# SMPS.net
KiCad netlist of a schematic drawn in Altium Designer
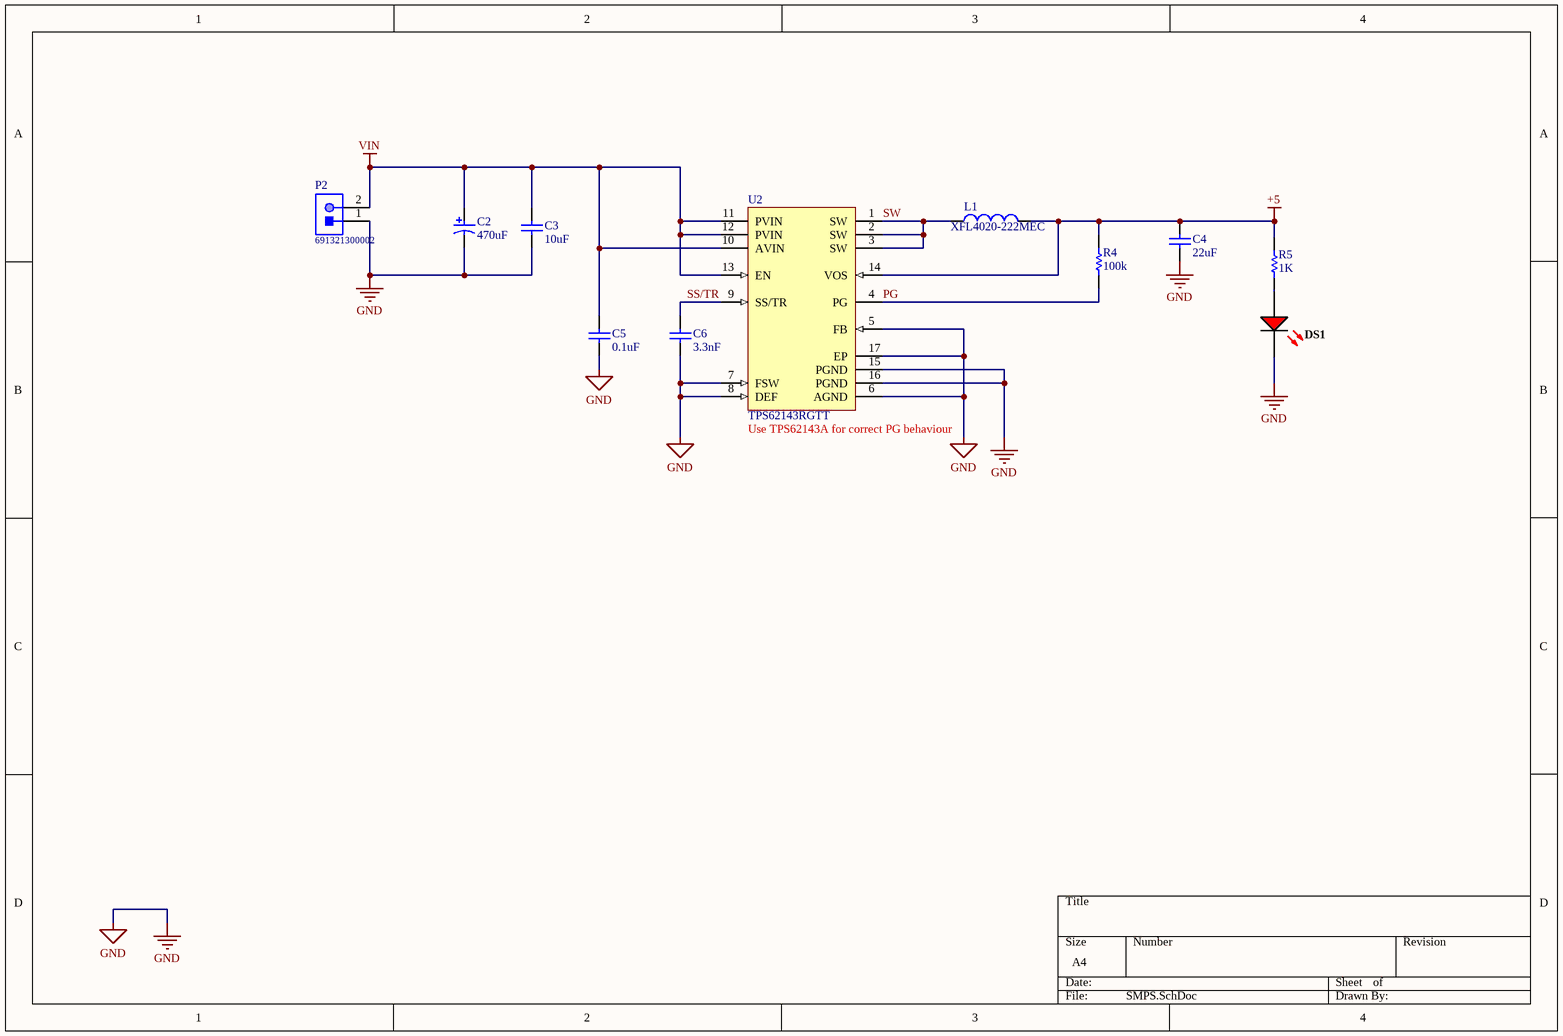
[diagram p0: SMPS.SchDoc]

(export (version "E")
  (design (tool "Eeschema 10.0.6"))
  (components
    (comp (ref "C2")
      (value "470uF")
      (footprint "PNSC-FK-V-F_V")
      (fields (field (name "MANUFACTURER") "Panasonic"))
      (libsource (lib "Altium Content Vault") (part "CAP-P-2"))
    )
    (comp (ref "C3")
      (value "10uF")
      (footprint "CAPC1210(3225)210_M")
      (description "CAP 10uF 35V ±20% 1210 (3225 Metric) Thickness 2.1mm SMD")
      (fields (field (name "TOLERANCE") "Â±20%"))
      (libsource (lib "Altium Content Vault") (part "CAP"))
    )
    (comp (ref "C4")
      (value "22uF")
      (footprint "CAPC2013X95X45ML15T25")
      (fields (field (name "MANUFACTURER") "Murata") (field (name "PART NUMBER") "GRM219R61A226MEA0D"))
      (libsource (lib "Altium Content Vault") (part "CAP"))
    )
    (comp (ref "C5")
      (value "0.1uF")
      (footprint "CAPC1608X87X35NL15T15")
      (fields (field (name "PART NUMBER") "C0603X104K5RACTU") (field (name "MANUFACTURER") "Kemet"))
      (libsource (lib "Altium Content Vault") (part "CAP"))
    )
    (comp (ref "C6")
      (value "3.3nF")
      (footprint "CAPC1608X87X35NL15T15")
      (fields (field (name "PART NUMBER") "C0603C332K5RAC7867") (field (name "MANUFACTURER") "Kemet"))
      (libsource (lib "Altium Content Vault") (part "CAP"))
    )
    (comp (ref "DS1")
      (value "APG1608SURKC/T")
      (footprint "KING-LED0603-25-RED_V")
      (fields (field (name "MANUFACTURER") "Kingbright"))
      (libsource (lib "Altium Content Vault") (part "KING-LED_RED_A1K2-2"))
    )
    (comp (ref "L1")
      (value "XFL4020-222MEC")
      (footprint "COIL-IND-2_V")
      (fields (field (name "MANUFACTURER") "Coilcraft") (field (name "TOLERANCE") "20%"))
      (libsource (lib "Altium Content Vault") (part "IND-2"))
    )
    (comp (ref "P2")
      (value "691321300002")
      (footprint "691321300002")
      (description "Serie 321 - 3.81mm Vertical PCB Header WR-TBL, 2 pin")
      (fields (field (name "MANUFACTURER") "Wurth Elektronik") (field (name "PUBLISHER") "WurthElektronik"))
      (libsource (lib "Altium Content Vault") (part "WE-CN-1P-M-R2"))
    )
    (comp (ref "R4")
      (value "100k")
      (footprint "RESC1608X55X25ML10T15")
      (description "Chip Resistor, 100 KOhm, +/- 1%, 0.1 W, -55 to 155 degC, 0603 (1608 Metric), RoHS, Tape and Reel")
      (fields (field (name "MANUFACTURER") "Yageo") (field (name "TOLERANCE") "1%"))
      (libsource (lib "Altium Content Vault") (part "RES-2"))
    )
    (comp (ref "R5")
      (value "1K")
      (footprint "RESC1608X55X30LL15T15")
      (fields (field (name "PART NUMBER") "ERJ-3EKF1001V") (field (name "MANUFACTURER") "Panasonic"))
      (libsource (lib "Altium Content Vault") (part "RES"))
    )
    (comp (ref "U2")
      (value "TPS62143RGTT")
      (footprint "RGT0016C_V")
      (fields (field (name "MANUFACTURER") "Texas Instruments"))
      (libsource (lib "Altium Content Vault") (part "TI-TPS62143RGT16-1700X1700TP"))
    )
  )
  (nets
    (net (code "1") (name "+5") (class "Default")
      (node (ref "C4") (pin "2") (pinfunction "2_2") (pintype "passive"))
      (node (ref "L1") (pin "2") (pinfunction "2_2") (pintype "passive"))
      (node (ref "R4") (pin "2") (pinfunction "2_2") (pintype "passive"))
      (node (ref "R5") (pin "2") (pinfunction "2_2") (pintype "passive"))
      (node (ref "U2") (pin "14") (pinfunction "VOS_14") (pintype "input"))
    )
    (net (code "2") (name "/PG") (class "Default")
      (node (ref "R4") (pin "1") (pinfunction "1_1") (pintype "passive"))
      (node (ref "U2") (pin "4") (pinfunction "PG_4") (pintype "tri_state"))
    )
    (net (code "3") (name "/SS{slash}TR") (class "Default")
      (node (ref "C6") (pin "2") (pinfunction "2_2") (pintype "passive"))
      (node (ref "U2") (pin "9") (pinfunction "SS/TR_9") (pintype "input"))
    )
    (net (code "4") (name "/SW") (class "Default")
      (node (ref "L1") (pin "1") (pinfunction "1_1") (pintype "passive"))
      (node (ref "U2") (pin "1") (pinfunction "SW_1") (pintype "power_in"))
      (node (ref "U2") (pin "2") (pinfunction "SW_2") (pintype "power_in"))
      (node (ref "U2") (pin "3") (pinfunction "SW_3") (pintype "power_in"))
    )
    (net (code "5") (name "GND") (class "Default")
      (node (ref "C2") (pin "2") (pinfunction "2_2") (pintype "passive"))
      (node (ref "C3") (pin "1") (pinfunction "1_1") (pintype "passive"))
      (node (ref "C4") (pin "1") (pinfunction "1_1") (pintype "passive"))
      (node (ref "C5") (pin "2") (pinfunction "2_2") (pintype "passive"))
      (node (ref "C6") (pin "1") (pinfunction "1_1") (pintype "passive"))
      (node (ref "DS1") (pin "2") (pinfunction "K_2") (pintype "passive"))
      (node (ref "P2") (pin "1") (pinfunction "1_1") (pintype "passive"))
      (node (ref "U2") (pin "15") (pinfunction "PGND_15") (pintype "power_in"))
      (node (ref "U2") (pin "16") (pinfunction "PGND_16") (pintype "power_in"))
      (node (ref "U2") (pin "17") (pinfunction "EP_17") (pintype "power_in"))
      (node (ref "U2") (pin "5") (pinfunction "FB_5") (pintype "input"))
      (node (ref "U2") (pin "6") (pinfunction "AGND_6") (pintype "power_in"))
      (node (ref "U2") (pin "7") (pinfunction "FSW_7") (pintype "input"))
      (node (ref "U2") (pin "8") (pinfunction "DEF_8") (pintype "input"))
    )
    (net (code "6") (name "Net-(DS1-A)") (class "Default")
      (node (ref "DS1") (pin "1") (pinfunction "A_1") (pintype "passive"))
      (node (ref "R5") (pin "1") (pinfunction "1_1") (pintype "passive"))
    )
    (net (code "7") (name "VIN") (class "Default")
      (node (ref "C2") (pin "1") (pinfunction "1_1") (pintype "passive"))
      (node (ref "C3") (pin "2") (pinfunction "2_2") (pintype "passive"))
      (node (ref "C5") (pin "1") (pinfunction "1_1") (pintype "passive"))
      (node (ref "P2") (pin "2") (pinfunction "2_2") (pintype "passive"))
      (node (ref "U2") (pin "10") (pinfunction "AVIN_10") (pintype "power_in"))
      (node (ref "U2") (pin "11") (pinfunction "PVIN_11") (pintype "power_in"))
      (node (ref "U2") (pin "12") (pinfunction "PVIN_12") (pintype "power_in"))
      (node (ref "U2") (pin "13") (pinfunction "EN_13") (pintype "input"))
    )
  )
)
